# Fiber_interlock.net
KiCad netlist of a schematic drawn in Altium Designer
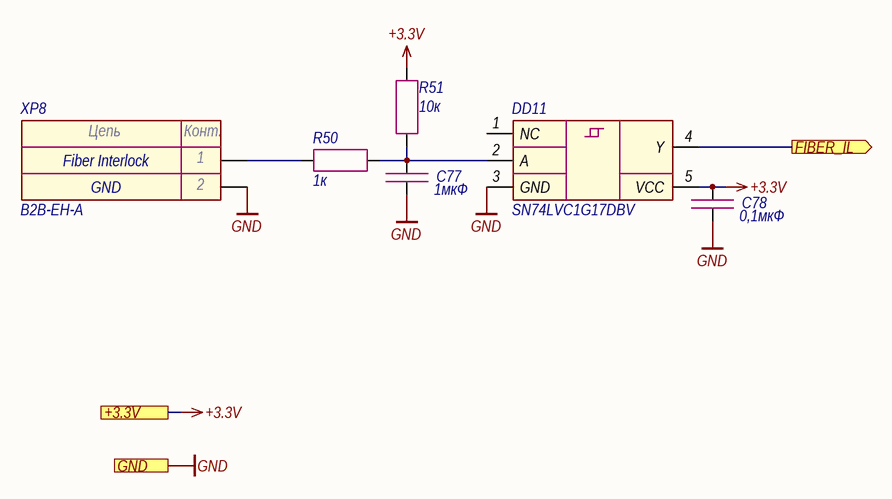
[diagram p0: Fiber_interlock.SchDoc]

(export (version "E")
  (design (tool "Eeschema 10.0.6"))
  (components
    (comp (ref "C77")
      (value "1мкФ")
      (footprint "Pcb_library:CAP_0603")
      (fields (field (name "MANUFACTURER") "Murata"))
      (libsource (lib "Schem_library") (part "Capacitor"))
    )
    (comp (ref "C78")
      (value "0,1мкФ")
      (footprint "Pcb_library:CAP_0603")
      (fields (field (name "MANUFACTURER") "Murata"))
      (libsource (lib "Schem_library") (part "Capacitor"))
    )
    (comp (ref "DD11")
      (value "SN74LVC1G17DBV")
      (footprint "Pcb_library:SOT-23-5")
      (fields (field (name "MANUFACTURER") "Texas Instruments"))
      (libsource (lib "Schem_library") (part "SN74LVC1G17"))
    )
    (comp (ref "R50")
      (value "1к")
      (footprint "Pcb_library:RES_0603")
      (fields (field (name "MANUFACTURER") "Yageo"))
      (libsource (lib "Schem_library") (part "Resistor"))
    )
    (comp (ref "R51")
      (value "10к")
      (footprint "Pcb_library:RES_0603")
      (fields (field (name "MANUFACTURER") "Yageo"))
      (libsource (lib "Schem_library") (part "Resistor"))
    )
    (comp (ref "XP8")
      (value "B2B-EH-A")
      (footprint "Pcb_library:B2B-EH-A")
      (fields (field (name "MANUFACTURER") "JST"))
      (libsource (lib "Schem_library") (part "Connector-2"))
    )
  )
  (nets
    (net (code "1") (name "+3.3V") (class "Default")
      (node (ref "C78") (pin "1") (pinfunction "1_1") (pintype "passive"))
      (node (ref "DD11") (pin "5") (pinfunction "VCC_5") (pintype "passive"))
      (node (ref "R51") (pin "2") (pinfunction "2_2") (pintype "passive"))
    )
    (net (code "2") (name "/FIBER_IL") (class "Default")
      (node (ref "DD11") (pin "4") (pinfunction "Y_4") (pintype "passive"))
    )
    (net (code "3") (name "GND") (class "Default")
      (node (ref "C77") (pin "2") (pinfunction "2_2") (pintype "passive"))
      (node (ref "C78") (pin "2") (pinfunction "2_2") (pintype "passive"))
      (node (ref "DD11") (pin "3") (pinfunction "GND_3") (pintype "passive"))
      (node (ref "XP8") (pin "2") (pintype "passive"))
    )
    (net (code "4") (name "Net-(DD11-A)") (class "Default")
      (node (ref "C77") (pin "1") (pinfunction "1_1") (pintype "passive"))
      (node (ref "DD11") (pin "2") (pinfunction "A_2") (pintype "passive"))
      (node (ref "R50") (pin "2") (pinfunction "2_2") (pintype "passive"))
      (node (ref "R51") (pin "1") (pinfunction "1_1") (pintype "passive"))
    )
    (net (code "5") (name "Net-(R50-Pad1)") (class "Default")
      (node (ref "R50") (pin "1") (pinfunction "1_1") (pintype "passive"))
      (node (ref "XP8") (pin "1") (pintype "passive"))
    )
    (net (code "6") (name "unconnected-(DD11-NC-Pad1)") (class "Default")
      (node (ref "DD11") (pin "1") (pinfunction "NC_1") (pintype "passive"))
    )
  )
)
